# batin.net
KiCad netlist of a schematic drawn in EAGLE
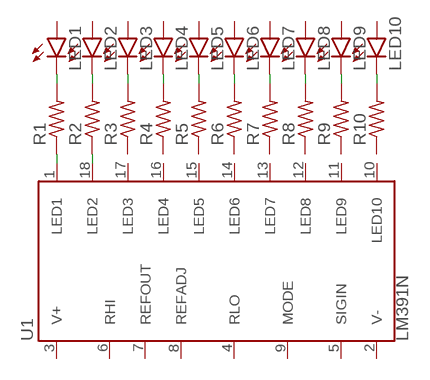
[diagram p0: schematic, sheet 1]

(export (version "E")
  (design (tool "Eeschema 10.0.6"))
  (components
    (comp (ref "LED1")
      (value "LED5MM")
      (footprint "eagle-import:LED5MM")
      (libsource (lib "eagle-import") (part "LED5MM"))
    )
    (comp (ref "LED2")
      (value "LED5MM")
      (footprint "eagle-import:LED5MM")
      (libsource (lib "eagle-import") (part "LED5MM"))
    )
    (comp (ref "LED3")
      (value "LED5MM")
      (footprint "eagle-import:LED5MM")
      (libsource (lib "eagle-import") (part "LED5MM"))
    )
    (comp (ref "LED4")
      (value "LED5MM")
      (footprint "eagle-import:LED5MM")
      (libsource (lib "eagle-import") (part "LED5MM"))
    )
    (comp (ref "LED5")
      (value "LED5MM")
      (footprint "eagle-import:LED5MM")
      (libsource (lib "eagle-import") (part "LED5MM"))
    )
    (comp (ref "LED6")
      (value "LED5MM")
      (footprint "eagle-import:LED5MM")
      (libsource (lib "eagle-import") (part "LED5MM"))
    )
    (comp (ref "LED7")
      (value "LED5MM")
      (footprint "eagle-import:LED5MM")
      (libsource (lib "eagle-import") (part "LED5MM"))
    )
    (comp (ref "LED8")
      (value "LED5MM")
      (footprint "eagle-import:LED5MM")
      (libsource (lib "eagle-import") (part "LED5MM"))
    )
    (comp (ref "LED9")
      (value "LED5MM")
      (footprint "eagle-import:LED5MM")
      (libsource (lib "eagle-import") (part "LED5MM"))
    )
    (comp (ref "LED10")
      (value "LED5MM")
      (footprint "eagle-import:LED5MM")
      (libsource (lib "eagle-import") (part "LED5MM"))
    )
    (comp (ref "R1")
      (value "R-US_0204/7")
      (footprint "eagle-import:0204_7")
      (libsource (lib "eagle-import") (part "R-US_0204/7"))
    )
    (comp (ref "R2")
      (value "R-US_0204/7")
      (footprint "eagle-import:0204_7")
      (libsource (lib "eagle-import") (part "R-US_0204/7"))
    )
    (comp (ref "R3")
      (value "R-US_0204/7")
      (footprint "eagle-import:0204_7")
      (libsource (lib "eagle-import") (part "R-US_0204/7"))
    )
    (comp (ref "R4")
      (value "R-US_0204/7")
      (footprint "eagle-import:0204_7")
      (libsource (lib "eagle-import") (part "R-US_0204/7"))
    )
    (comp (ref "R5")
      (value "R-US_0204/7")
      (footprint "eagle-import:0204_7")
      (libsource (lib "eagle-import") (part "R-US_0204/7"))
    )
    (comp (ref "R6")
      (value "R-US_0204/7")
      (footprint "eagle-import:0204_7")
      (libsource (lib "eagle-import") (part "R-US_0204/7"))
    )
    (comp (ref "R7")
      (value "R-US_0204/7")
      (footprint "eagle-import:0204_7")
      (libsource (lib "eagle-import") (part "R-US_0204/7"))
    )
    (comp (ref "R8")
      (value "R-US_0204/7")
      (footprint "eagle-import:0204_7")
      (libsource (lib "eagle-import") (part "R-US_0204/7"))
    )
    (comp (ref "R9")
      (value "R-US_0204/7")
      (footprint "eagle-import:0204_7")
      (libsource (lib "eagle-import") (part "R-US_0204/7"))
    )
    (comp (ref "R10")
      (value "R-US_0204/7")
      (footprint "eagle-import:0204_7")
      (libsource (lib "eagle-import") (part "R-US_0204/7"))
    )
    (comp (ref "U1")
      (value "LM391N")
      (footprint "eagle-import:DIL18")
      (libsource (lib "eagle-import") (part "LM391N"))
    )
  )
  (nets
    (net (code "1") (name "/V+") (class "Default")
      (node (ref "U1") (pin "3") (pinfunction "V+_3") (pintype "power_in"))
    )
    (net (code "2") (name "/V-") (class "Default")
      (node (ref "U1") (pin "2") (pinfunction "V-_2") (pintype "power_in"))
    )
    (net (code "3") (name "Net-(LED1-C)") (class "Default")
      (node (ref "LED1") (pin "K") (pinfunction "C_K") (pintype "passive"))
      (node (ref "R1") (pin "2") (pinfunction "2_2") (pintype "passive"))
    )
    (net (code "4") (name "Net-(LED2-C)") (class "Default")
      (node (ref "LED2") (pin "K") (pinfunction "C_K") (pintype "passive"))
      (node (ref "R2") (pin "2") (pinfunction "2_2") (pintype "passive"))
    )
    (net (code "5") (name "Net-(LED3-C)") (class "Default")
      (node (ref "LED3") (pin "K") (pinfunction "C_K") (pintype "passive"))
      (node (ref "R3") (pin "2") (pinfunction "2_2") (pintype "passive"))
    )
    (net (code "6") (name "Net-(LED4-C)") (class "Default")
      (node (ref "LED4") (pin "K") (pinfunction "C_K") (pintype "passive"))
      (node (ref "R4") (pin "2") (pinfunction "2_2") (pintype "passive"))
    )
    (net (code "7") (name "Net-(LED5-C)") (class "Default")
      (node (ref "LED5") (pin "K") (pinfunction "C_K") (pintype "passive"))
      (node (ref "R5") (pin "2") (pinfunction "2_2") (pintype "passive"))
    )
    (net (code "8") (name "Net-(LED6-C)") (class "Default")
      (node (ref "LED6") (pin "K") (pinfunction "C_K") (pintype "passive"))
      (node (ref "R6") (pin "2") (pinfunction "2_2") (pintype "passive"))
    )
    (net (code "9") (name "Net-(LED7-C)") (class "Default")
      (node (ref "LED7") (pin "K") (pinfunction "C_K") (pintype "passive"))
      (node (ref "R7") (pin "2") (pinfunction "2_2") (pintype "passive"))
    )
    (net (code "10") (name "Net-(LED8-C)") (class "Default")
      (node (ref "LED8") (pin "K") (pinfunction "C_K") (pintype "passive"))
      (node (ref "R8") (pin "2") (pinfunction "2_2") (pintype "passive"))
    )
    (net (code "11") (name "Net-(LED9-C)") (class "Default")
      (node (ref "LED9") (pin "K") (pinfunction "C_K") (pintype "passive"))
      (node (ref "R9") (pin "2") (pinfunction "2_2") (pintype "passive"))
    )
    (net (code "12") (name "Net-(LED10-C)") (class "Default")
      (node (ref "LED10") (pin "K") (pinfunction "C_K") (pintype "passive"))
      (node (ref "R10") (pin "2") (pinfunction "2_2") (pintype "passive"))
    )
    (net (code "13") (name "Net-(U1-LED1)") (class "Default")
      (node (ref "R1") (pin "1") (pinfunction "1_1") (pintype "passive"))
      (node (ref "U1") (pin "1") (pinfunction "LED1_1") (pintype "output"))
    )
    (net (code "14") (name "Net-(U1-LED2)") (class "Default")
      (node (ref "R2") (pin "1") (pinfunction "1_1") (pintype "passive"))
      (node (ref "U1") (pin "18") (pinfunction "LED2_18") (pintype "output"))
    )
    (net (code "15") (name "unconnected-(LED1-PadA)") (class "Default")
      (node (ref "LED1") (pin "A") (pinfunction "A_A") (pintype "passive"))
    )
    (net (code "16") (name "unconnected-(LED2-PadA)") (class "Default")
      (node (ref "LED2") (pin "A") (pinfunction "A_A") (pintype "passive"))
    )
    (net (code "17") (name "unconnected-(LED3-PadA)") (class "Default")
      (node (ref "LED3") (pin "A") (pinfunction "A_A") (pintype "passive"))
    )
    (net (code "18") (name "unconnected-(LED4-PadA)") (class "Default")
      (node (ref "LED4") (pin "A") (pinfunction "A_A") (pintype "passive"))
    )
    (net (code "19") (name "unconnected-(LED5-PadA)") (class "Default")
      (node (ref "LED5") (pin "A") (pinfunction "A_A") (pintype "passive"))
    )
    (net (code "20") (name "unconnected-(LED6-PadA)") (class "Default")
      (node (ref "LED6") (pin "A") (pinfunction "A_A") (pintype "passive"))
    )
    (net (code "21") (name "unconnected-(LED7-PadA)") (class "Default")
      (node (ref "LED7") (pin "A") (pinfunction "A_A") (pintype "passive"))
    )
    (net (code "22") (name "unconnected-(LED8-PadA)") (class "Default")
      (node (ref "LED8") (pin "A") (pinfunction "A_A") (pintype "passive"))
    )
    (net (code "23") (name "unconnected-(LED9-PadA)") (class "Default")
      (node (ref "LED9") (pin "A") (pinfunction "A_A") (pintype "passive"))
    )
    (net (code "24") (name "unconnected-(LED10-PadA)") (class "Default")
      (node (ref "LED10") (pin "A") (pinfunction "A_A") (pintype "passive"))
    )
    (net (code "25") (name "unconnected-(R3-Pad1)") (class "Default")
      (node (ref "R3") (pin "1") (pinfunction "1_1") (pintype "passive"))
    )
    (net (code "26") (name "unconnected-(R4-Pad1)") (class "Default")
      (node (ref "R4") (pin "1") (pinfunction "1_1") (pintype "passive"))
    )
    (net (code "27") (name "unconnected-(R5-Pad1)") (class "Default")
      (node (ref "R5") (pin "1") (pinfunction "1_1") (pintype "passive"))
    )
    (net (code "28") (name "unconnected-(R6-Pad1)") (class "Default")
      (node (ref "R6") (pin "1") (pinfunction "1_1") (pintype "passive"))
    )
    (net (code "29") (name "unconnected-(R7-Pad1)") (class "Default")
      (node (ref "R7") (pin "1") (pinfunction "1_1") (pintype "passive"))
    )
    (net (code "30") (name "unconnected-(R8-Pad1)") (class "Default")
      (node (ref "R8") (pin "1") (pinfunction "1_1") (pintype "passive"))
    )
    (net (code "31") (name "unconnected-(R9-Pad1)") (class "Default")
      (node (ref "R9") (pin "1") (pinfunction "1_1") (pintype "passive"))
    )
    (net (code "32") (name "unconnected-(R10-Pad1)") (class "Default")
      (node (ref "R10") (pin "1") (pinfunction "1_1") (pintype "passive"))
    )
    (net (code "33") (name "unconnected-(U1-LED3-Pad17)") (class "Default")
      (node (ref "U1") (pin "17") (pinfunction "LED3_17") (pintype "output"))
    )
    (net (code "34") (name "unconnected-(U1-LED4-Pad16)") (class "Default")
      (node (ref "U1") (pin "16") (pinfunction "LED4_16") (pintype "output"))
    )
    (net (code "35") (name "unconnected-(U1-LED5-Pad15)") (class "Default")
      (node (ref "U1") (pin "15") (pinfunction "LED5_15") (pintype "output"))
    )
    (net (code "36") (name "unconnected-(U1-LED6-Pad14)") (class "Default")
      (node (ref "U1") (pin "14") (pinfunction "LED6_14") (pintype "output"))
    )
    (net (code "37") (name "unconnected-(U1-LED7-Pad13)") (class "Default")
      (node (ref "U1") (pin "13") (pinfunction "LED7_13") (pintype "output"))
    )
    (net (code "38") (name "unconnected-(U1-LED8-Pad12)") (class "Default")
      (node (ref "U1") (pin "12") (pinfunction "LED8_12") (pintype "output"))
    )
    (net (code "39") (name "unconnected-(U1-LED9-Pad11)") (class "Default")
      (node (ref "U1") (pin "11") (pinfunction "LED9_11") (pintype "output"))
    )
    (net (code "40") (name "unconnected-(U1-LED10-Pad10)") (class "Default")
      (node (ref "U1") (pin "10") (pinfunction "LED10_10") (pintype "output"))
    )
    (net (code "41") (name "unconnected-(U1-MODE-Pad9)") (class "Default")
      (node (ref "U1") (pin "9") (pinfunction "MODE_9") (pintype "input"))
    )
    (net (code "42") (name "unconnected-(U1-REFADJ-Pad8)") (class "Default")
      (node (ref "U1") (pin "8") (pinfunction "REFADJ_8") (pintype "passive"))
    )
    (net (code "43") (name "unconnected-(U1-REFOUT-Pad7)") (class "Default")
      (node (ref "U1") (pin "7") (pinfunction "REFOUT_7") (pintype "output"))
    )
    (net (code "44") (name "unconnected-(U1-RHI-Pad6)") (class "Default")
      (node (ref "U1") (pin "6") (pinfunction "RHI_6") (pintype "input"))
    )
    (net (code "45") (name "unconnected-(U1-RLO-Pad4)") (class "Default")
      (node (ref "U1") (pin "4") (pinfunction "RLO_4") (pintype "input"))
    )
    (net (code "46") (name "unconnected-(U1-SIGIN-Pad5)") (class "Default")
      (node (ref "U1") (pin "5") (pinfunction "SIGIN_5") (pintype "input"))
    )
  )
)
